# schematic.net
KiCad netlist of a schematic drawn in EasyEDA
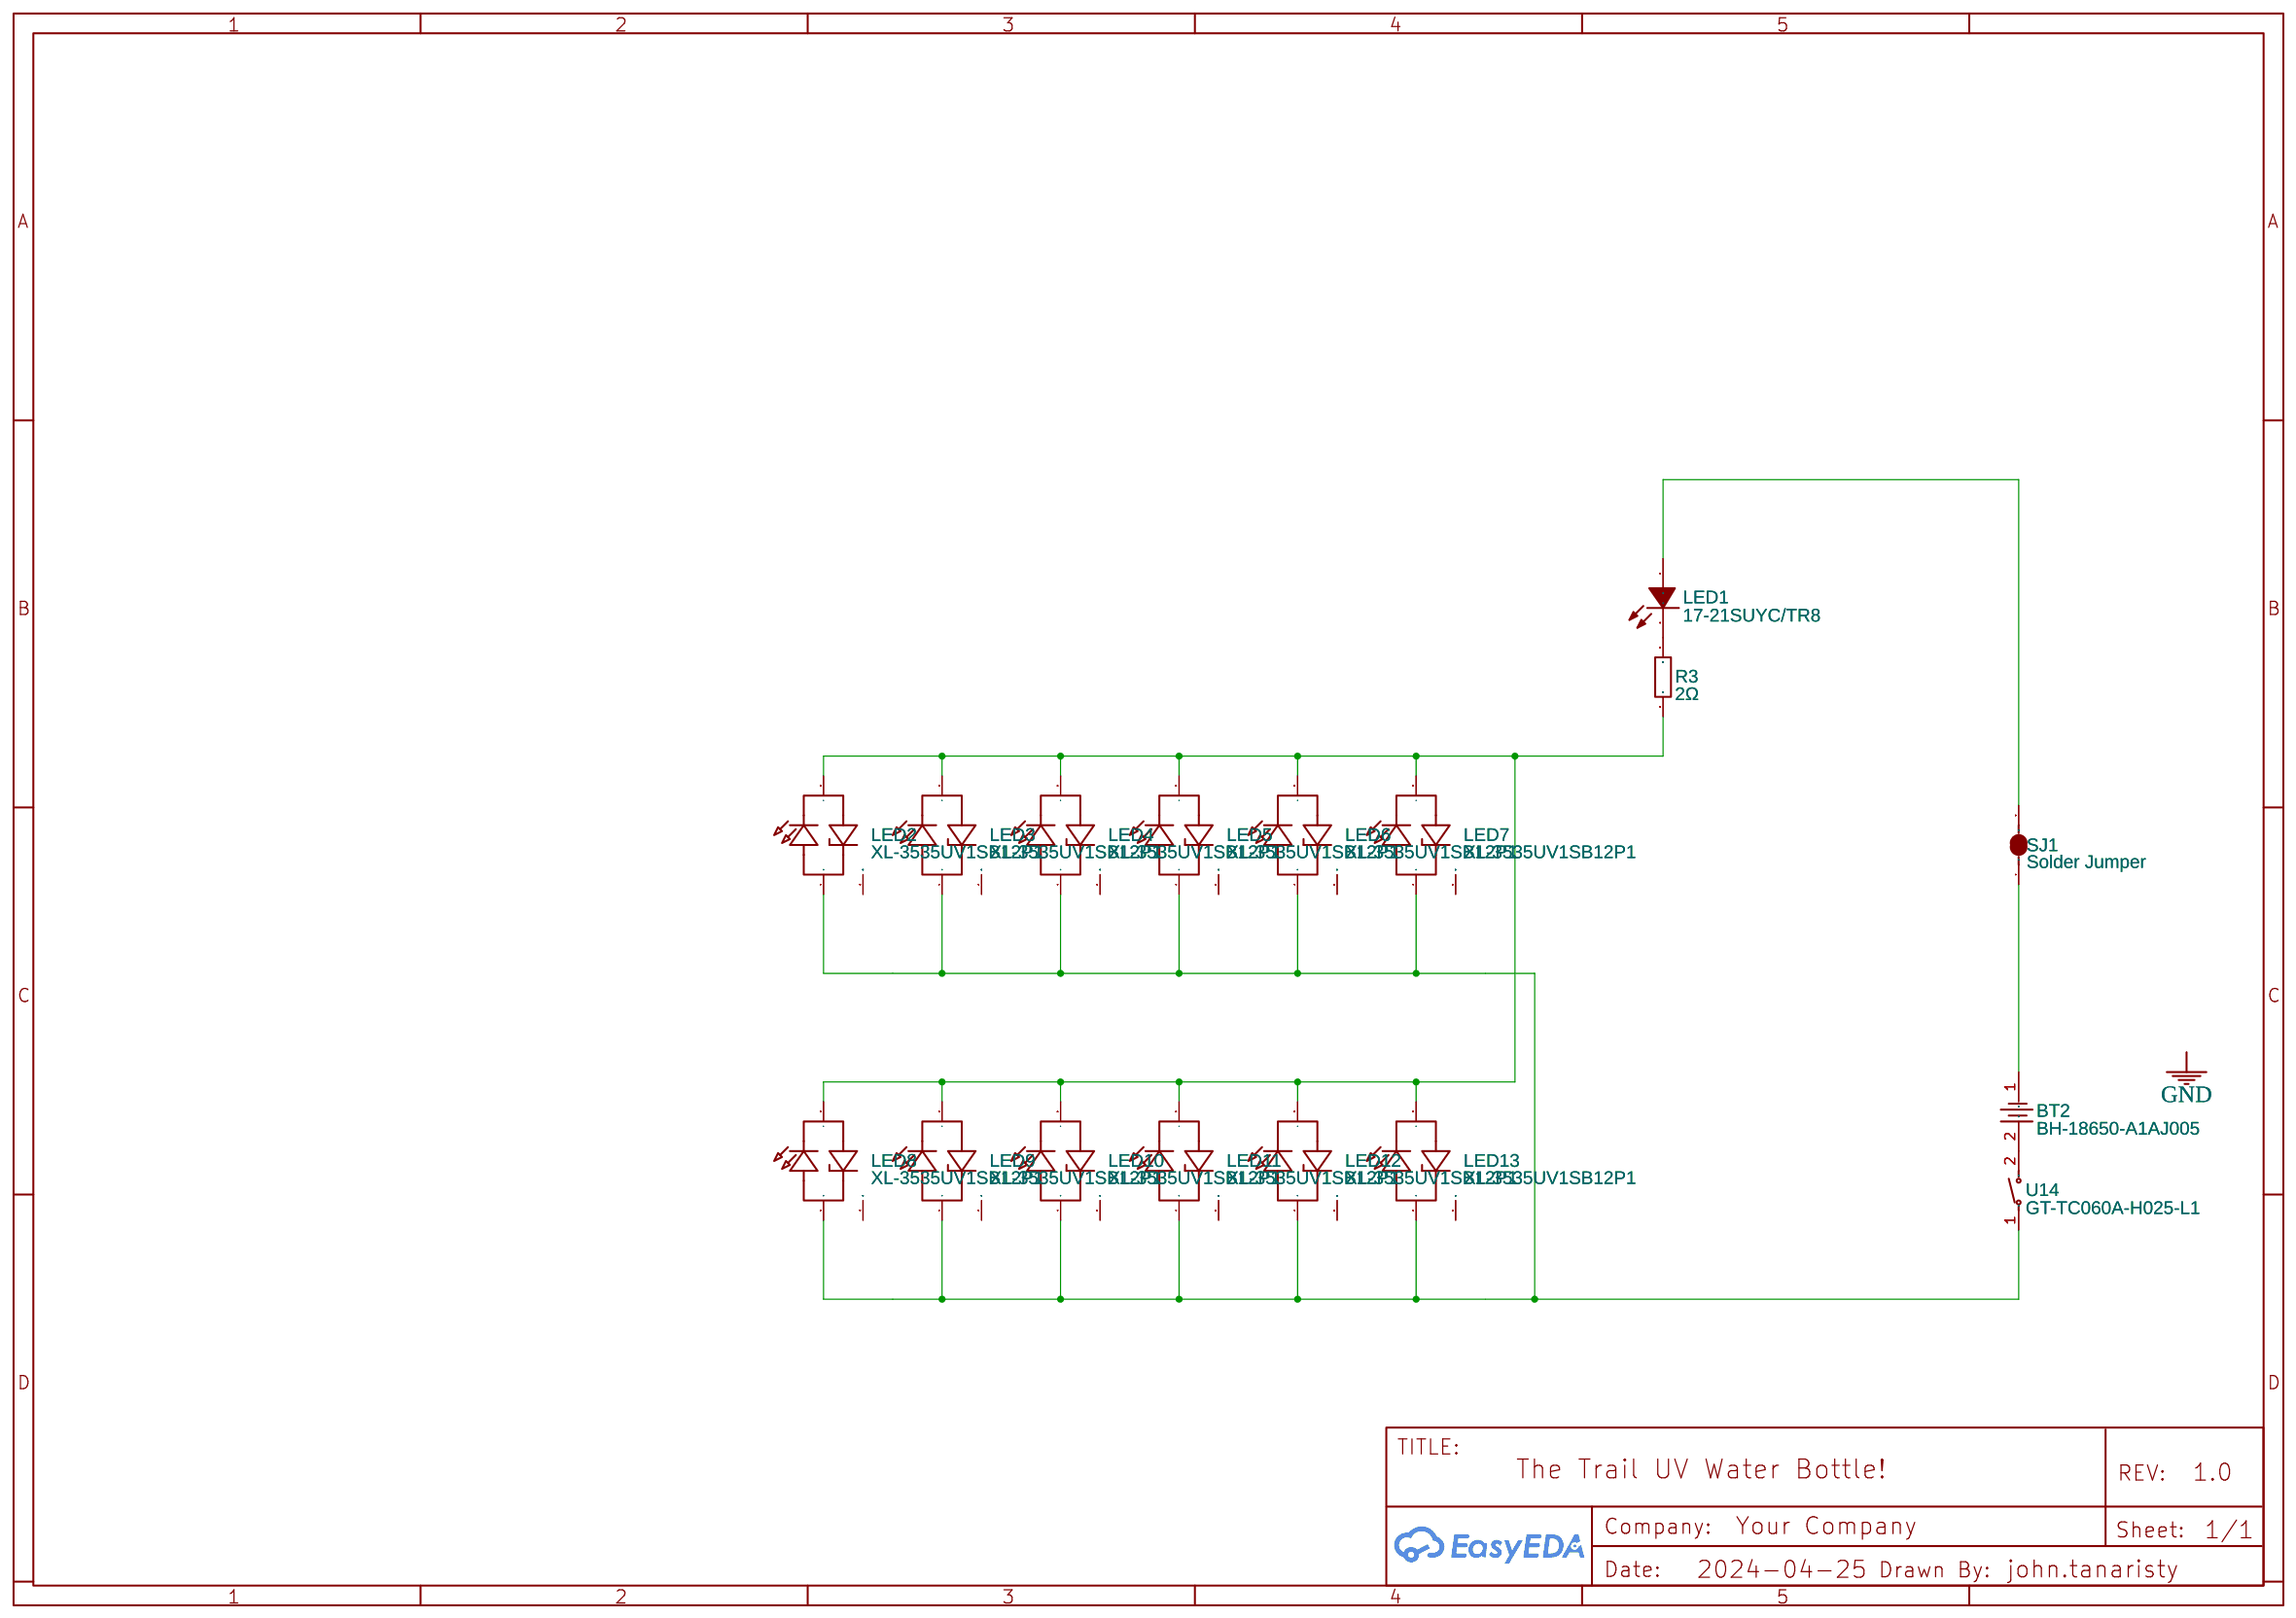
[diagram p0: schematic sheet]

(export (version "E")
  (design (tool "Eeschema 10.0.6"))
  (components
    (comp (ref "BT2")
      (value "BH-18650-A1AJ005")
      (fields (field (name "Manufacturer") "MYOUNG(美阳)"))
      (libsource (lib "") (part "BH-18650-A1AJ005"))
    )
    (comp (ref "LED1")
      (value "17-21SUYC/TR8")
      (fields (field (name "Manufacturer Part") "KT-0805黄灯") (field (name "Manufacturer") "KENTO"))
      (libsource (lib "") (part "17-21SUYC/TR8"))
    )
    (comp (ref "LED2")
      (value "XL-3535UV1SB12P1")
      (fields (field (name "Manufacturer") "XINGLIGHT(成兴光)"))
      (libsource (lib "") (part "XL-3535UV1SB12P1"))
    )
    (comp (ref "LED3")
      (value "XL-3535UV1SB12P1")
      (fields (field (name "Manufacturer") "XINGLIGHT(成兴光)"))
      (libsource (lib "") (part "XL-3535UV1SB12P1"))
    )
    (comp (ref "LED4")
      (value "XL-3535UV1SB12P1")
      (fields (field (name "Manufacturer") "XINGLIGHT(成兴光)"))
      (libsource (lib "") (part "XL-3535UV1SB12P1"))
    )
    (comp (ref "LED5")
      (value "XL-3535UV1SB12P1")
      (fields (field (name "Manufacturer") "XINGLIGHT(成兴光)"))
      (libsource (lib "") (part "XL-3535UV1SB12P1"))
    )
    (comp (ref "LED6")
      (value "XL-3535UV1SB12P1")
      (fields (field (name "Manufacturer") "XINGLIGHT(成兴光)"))
      (libsource (lib "") (part "XL-3535UV1SB12P1"))
    )
    (comp (ref "LED7")
      (value "XL-3535UV1SB12P1")
      (fields (field (name "Manufacturer") "XINGLIGHT(成兴光)"))
      (libsource (lib "") (part "XL-3535UV1SB12P1"))
    )
    (comp (ref "LED8")
      (value "XL-3535UV1SB12P1")
      (fields (field (name "Manufacturer") "XINGLIGHT(成兴光)"))
      (libsource (lib "") (part "XL-3535UV1SB12P1"))
    )
    (comp (ref "LED9")
      (value "XL-3535UV1SB12P1")
      (fields (field (name "Manufacturer") "XINGLIGHT(成兴光)"))
      (libsource (lib "") (part "XL-3535UV1SB12P1"))
    )
    (comp (ref "LED10")
      (value "XL-3535UV1SB12P1")
      (fields (field (name "Manufacturer") "XINGLIGHT(成兴光)"))
      (libsource (lib "") (part "XL-3535UV1SB12P1"))
    )
    (comp (ref "LED11")
      (value "XL-3535UV1SB12P1")
      (fields (field (name "Manufacturer") "XINGLIGHT(成兴光)"))
      (libsource (lib "") (part "XL-3535UV1SB12P1"))
    )
    (comp (ref "LED12")
      (value "XL-3535UV1SB12P1")
      (fields (field (name "Manufacturer") "XINGLIGHT(成兴光)"))
      (libsource (lib "") (part "XL-3535UV1SB12P1"))
    )
    (comp (ref "LED13")
      (value "XL-3535UV1SB12P1")
      (fields (field (name "Manufacturer") "XINGLIGHT(成兴光)"))
      (libsource (lib "") (part "XL-3535UV1SB12P1"))
    )
    (comp (ref "R3")
      (value "2Ω")
      (fields
        (field (name "Manufacturer Part") "0603WAF200KT5E")
        (field (name "Manufacturer") "UNI-ROYAL(厚声)")
      )
      (libsource (lib "") (part "0603WAF200KT5E"))
    )
    (comp (ref "SJ1") (value "Solder Jumper") (libsource (lib "") (part "Solder Jumper")))
    (comp (ref "U14")
      (value "GT-TC060A-H025-L1")
      (fields (field (name "Manufacturer") "G-Switch(品赞)"))
      (libsource (lib "") (part "GT-TC060A-H025-L1"))
    )
  )
  (nets
    (net (code "2") (name "Net-(BT2-Pad1)") (class "Default")
      (node (ref "BT2") (pin "1") (pinfunction "1_1") (pintype "input"))
      (node (ref "SJ1") (pin "1") (pinfunction "1_1") (pintype "unspecified"))
    )
    (net (code "3") (name "Net-(BT2-Pad2)") (class "Default")
      (node (ref "BT2") (pin "2") (pinfunction "2_2") (pintype "input"))
      (node (ref "U14") (pin "2") (pinfunction "2_2") (pintype "unspecified"))
    )
    (net (code "4") (name "Net-(LED1-+)") (class "Default")
      (node (ref "LED1") (pin "1") (pinfunction "+_1") (pintype "unspecified"))
      (node (ref "SJ1") (pin "2") (pinfunction "2_2") (pintype "unspecified"))
    )
    (net (code "5") (name "Net-(LED1--)") (class "Default")
      (node (ref "LED1") (pin "2") (pinfunction "-_2") (pintype "unspecified"))
      (node (ref "R3") (pin "2") (pinfunction "2_2") (pintype "input"))
    )
    (net (code "6") (name "Net-(LED10-+)") (class "Default")
      (node (ref "LED10") (pin "1") (pinfunction "+_1") (pintype "unspecified"))
      (node (ref "LED11") (pin "1") (pinfunction "+_1") (pintype "unspecified"))
      (node (ref "LED12") (pin "1") (pinfunction "+_1") (pintype "unspecified"))
      (node (ref "LED13") (pin "1") (pinfunction "+_1") (pintype "unspecified"))
      (node (ref "LED2") (pin "1") (pinfunction "+_1") (pintype "unspecified"))
      (node (ref "LED3") (pin "1") (pinfunction "+_1") (pintype "unspecified"))
      (node (ref "LED4") (pin "1") (pinfunction "+_1") (pintype "unspecified"))
      (node (ref "LED5") (pin "1") (pinfunction "+_1") (pintype "unspecified"))
      (node (ref "LED6") (pin "1") (pinfunction "+_1") (pintype "unspecified"))
      (node (ref "LED7") (pin "1") (pinfunction "+_1") (pintype "unspecified"))
      (node (ref "LED8") (pin "1") (pinfunction "+_1") (pintype "unspecified"))
      (node (ref "LED9") (pin "1") (pinfunction "+_1") (pintype "unspecified"))
      (node (ref "U14") (pin "1") (pinfunction "1_1") (pintype "unspecified"))
    )
    (net (code "7") (name "Net-(LED10--)") (class "Default")
      (node (ref "LED10") (pin "2") (pinfunction "-_2") (pintype "unspecified"))
      (node (ref "LED11") (pin "2") (pinfunction "-_2") (pintype "unspecified"))
      (node (ref "LED12") (pin "2") (pinfunction "-_2") (pintype "unspecified"))
      (node (ref "LED13") (pin "2") (pinfunction "-_2") (pintype "unspecified"))
      (node (ref "LED2") (pin "2") (pinfunction "-_2") (pintype "unspecified"))
      (node (ref "LED3") (pin "2") (pinfunction "-_2") (pintype "unspecified"))
      (node (ref "LED4") (pin "2") (pinfunction "-_2") (pintype "unspecified"))
      (node (ref "LED5") (pin "2") (pinfunction "-_2") (pintype "unspecified"))
      (node (ref "LED6") (pin "2") (pinfunction "-_2") (pintype "unspecified"))
      (node (ref "LED7") (pin "2") (pinfunction "-_2") (pintype "unspecified"))
      (node (ref "LED8") (pin "2") (pinfunction "-_2") (pintype "unspecified"))
      (node (ref "LED9") (pin "2") (pinfunction "-_2") (pintype "unspecified"))
      (node (ref "R3") (pin "1") (pinfunction "1_1") (pintype "input"))
    )
    (net (code "8") (name "unconnected-(LED2-Pad3)") (class "Default")
      (node (ref "LED2") (pin "3") (pinfunction "3_3") (pintype "unspecified"))
    )
    (net (code "9") (name "unconnected-(LED3-Pad3)") (class "Default")
      (node (ref "LED3") (pin "3") (pinfunction "3_3") (pintype "unspecified"))
    )
    (net (code "10") (name "unconnected-(LED4-Pad3)") (class "Default")
      (node (ref "LED4") (pin "3") (pinfunction "3_3") (pintype "unspecified"))
    )
    (net (code "11") (name "unconnected-(LED5-Pad3)") (class "Default")
      (node (ref "LED5") (pin "3") (pinfunction "3_3") (pintype "unspecified"))
    )
    (net (code "12") (name "unconnected-(LED6-Pad3)") (class "Default")
      (node (ref "LED6") (pin "3") (pinfunction "3_3") (pintype "unspecified"))
    )
    (net (code "13") (name "unconnected-(LED7-Pad3)") (class "Default")
      (node (ref "LED7") (pin "3") (pinfunction "3_3") (pintype "unspecified"))
    )
    (net (code "14") (name "unconnected-(LED8-Pad3)") (class "Default")
      (node (ref "LED8") (pin "3") (pinfunction "3_3") (pintype "unspecified"))
    )
    (net (code "15") (name "unconnected-(LED9-Pad3)") (class "Default")
      (node (ref "LED9") (pin "3") (pinfunction "3_3") (pintype "unspecified"))
    )
    (net (code "16") (name "unconnected-(LED10-Pad3)") (class "Default")
      (node (ref "LED10") (pin "3") (pinfunction "3_3") (pintype "unspecified"))
    )
    (net (code "17") (name "unconnected-(LED11-Pad3)") (class "Default")
      (node (ref "LED11") (pin "3") (pinfunction "3_3") (pintype "unspecified"))
    )
    (net (code "18") (name "unconnected-(LED12-Pad3)") (class "Default")
      (node (ref "LED12") (pin "3") (pinfunction "3_3") (pintype "unspecified"))
    )
    (net (code "19") (name "unconnected-(LED13-Pad3)") (class "Default")
      (node (ref "LED13") (pin "3") (pinfunction "3_3") (pintype "unspecified"))
    )
  )
)
